# CertStack.net
KiCad netlist of a schematic drawn in EAGLE
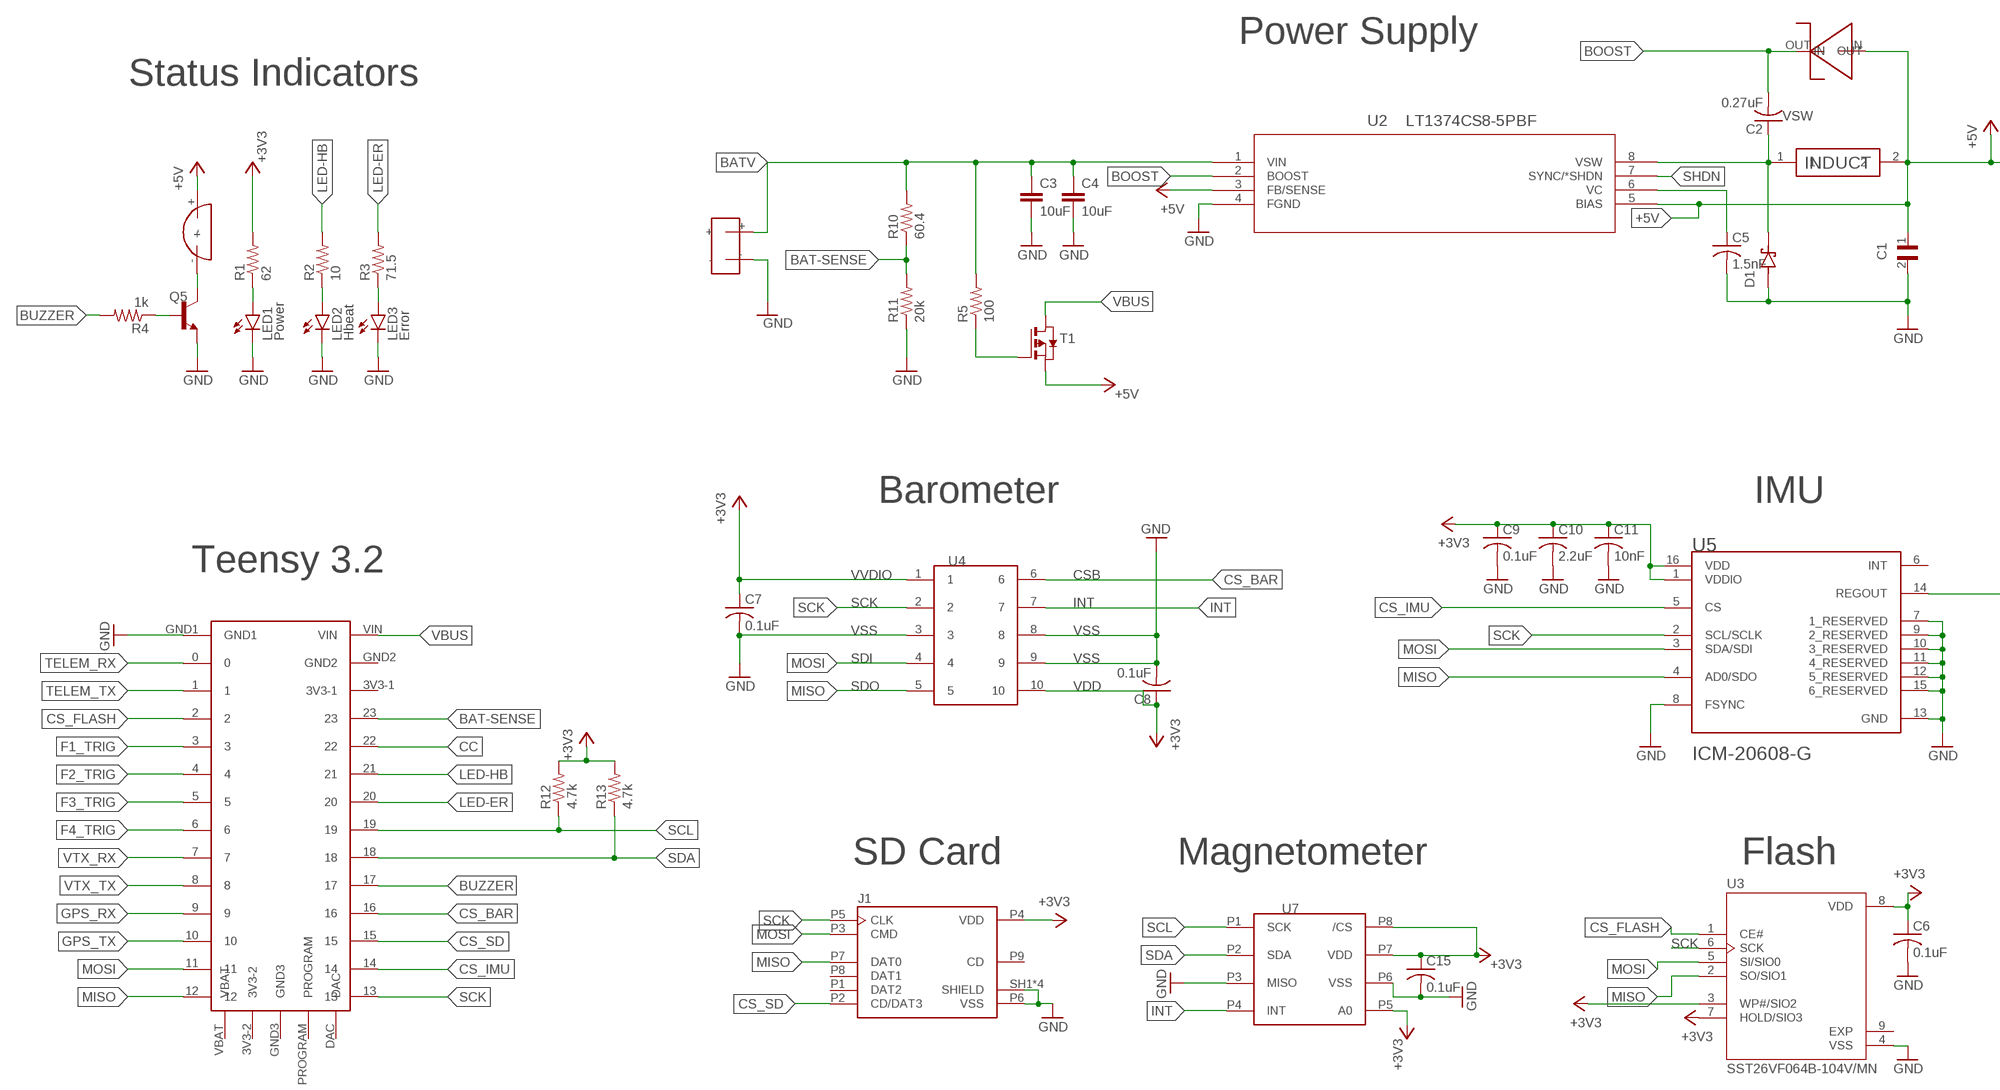
[diagram p0: schematic, sheet 1, part 1 of 2]
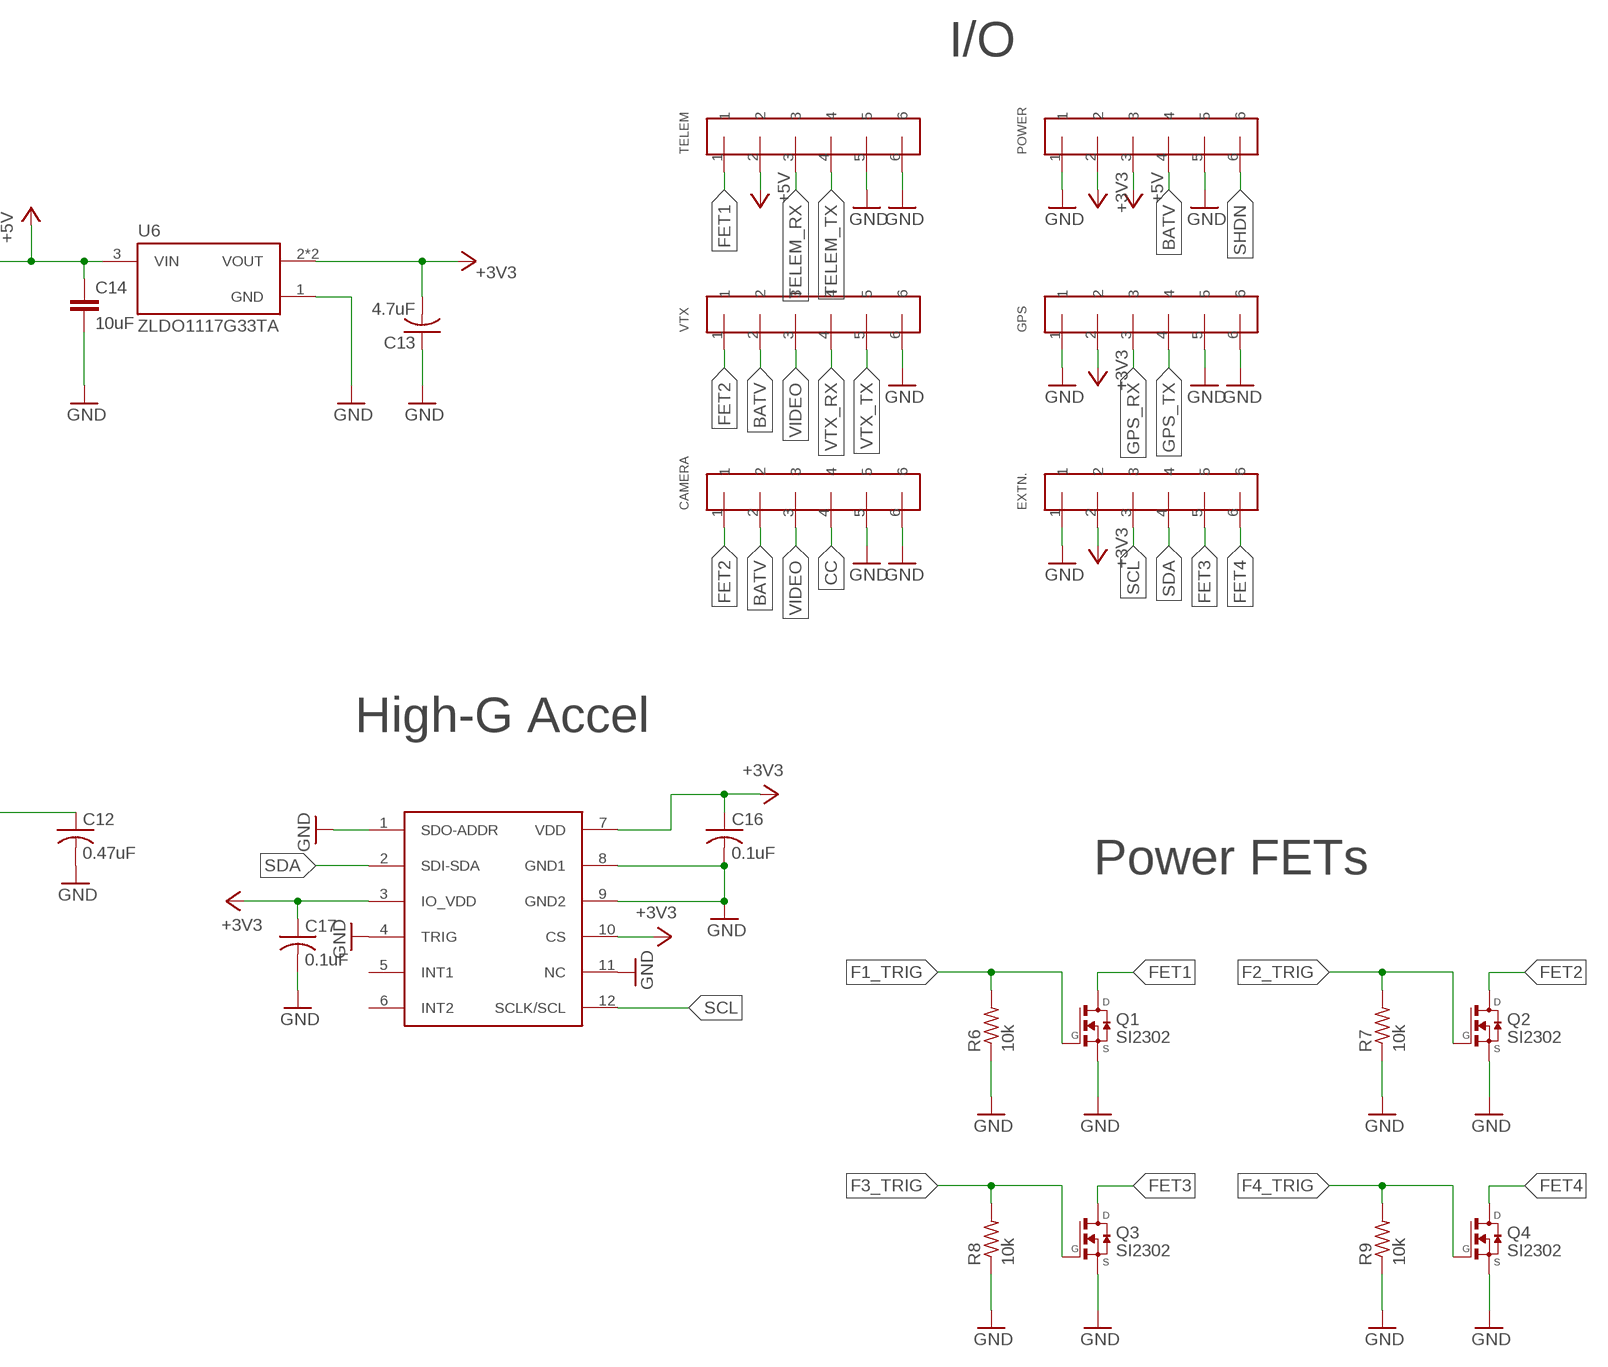
[diagram p1: schematic, sheet 1, part 2 of 2]

(export (version "E")
  (design (tool "Eeschema 10.0.6"))
  (components
    (comp (ref "BATT-CON")
      (value "PWR-AWG18")
      (footprint "eagle-import:PWR-AWG18")
      (libsource (lib "eagle-import") (part "PWR-AWG18"))
    )
    (comp (ref "C1")
      (value "T491X106K050AT")
      (footprint "eagle-import:CAPMP7343X430N")
      (fields (field (name "MF") "KEMET"))
      (libsource (lib "eagle-import") (part "T491X106K050AT"))
    )
    (comp (ref "C2")
      (value "0.27uF")
      (footprint "eagle-import:C0805")
      (libsource (lib "eagle-import") (part "C-USC0805"))
    )
    (comp (ref "C3")
      (value "10uF")
      (footprint "eagle-import:1206")
      (libsource (lib "eagle-import") (part "10UF-1206-6.3V-20%"))
    )
    (comp (ref "C4")
      (value "10uF")
      (footprint "eagle-import:1206")
      (libsource (lib "eagle-import") (part "10UF-1206-6.3V-20%"))
    )
    (comp (ref "C5")
      (value "1.5nF")
      (footprint "eagle-import:C0805")
      (libsource (lib "eagle-import") (part "C-USC0805"))
    )
    (comp (ref "C6")
      (value "0.1uF")
      (footprint "eagle-import:C0805")
      (libsource (lib "eagle-import") (part "C-USC0805"))
    )
    (comp (ref "C7")
      (value "0.1uF")
      (footprint "eagle-import:C0805")
      (libsource (lib "eagle-import") (part "C-USC0805"))
    )
    (comp (ref "C8")
      (value "0.1uF")
      (footprint "eagle-import:C0805")
      (libsource (lib "eagle-import") (part "C-USC0805"))
    )
    (comp (ref "C9")
      (value "0.1uF")
      (footprint "eagle-import:C0805")
      (libsource (lib "eagle-import") (part "C-USC0805"))
    )
    (comp (ref "C10")
      (value "2.2uF")
      (footprint "eagle-import:C0805")
      (libsource (lib "eagle-import") (part "C-USC0805"))
    )
    (comp (ref "C11")
      (value "10nF")
      (footprint "eagle-import:C0805")
      (libsource (lib "eagle-import") (part "C-USC0805"))
    )
    (comp (ref "C12")
      (value "0.47uF")
      (footprint "eagle-import:C0805")
      (libsource (lib "eagle-import") (part "C-USC0805"))
    )
    (comp (ref "C13")
      (value "4.7uF")
      (footprint "eagle-import:C0805")
      (libsource (lib "eagle-import") (part "C-USC0805"))
    )
    (comp (ref "C14")
      (value "10uF")
      (footprint "eagle-import:1206")
      (libsource (lib "eagle-import") (part "10UF-1206-6.3V-20%"))
    )
    (comp (ref "C15")
      (value "0.1uF")
      (footprint "eagle-import:C0805")
      (libsource (lib "eagle-import") (part "C-USC0805"))
    )
    (comp (ref "C16")
      (value "0.1uF")
      (footprint "eagle-import:C0805")
      (libsource (lib "eagle-import") (part "C-USC0805"))
    )
    (comp (ref "C17")
      (value "0.1uF")
      (footprint "eagle-import:C0805")
      (libsource (lib "eagle-import") (part "C-USC0805"))
    )
    (comp (ref "CAMERA")
      (value "JST-PH-6")
      (footprint "eagle-import:JST-PH-6")
      (libsource (lib "eagle-import") (part "JST-PH-6"))
    )
    (comp (ref "D1")
      (value "PMEG4020ETP,115")
      (footprint "eagle-import:SODFL4725X110N")
      (fields (field (name "MF") "Nexperia USA Inc."))
      (libsource (lib "eagle-import") (part "PMEG4020ETP,115"))
    )
    (comp (ref "D2")
      (value "DO-214AB")
      (footprint "eagle-import:DO-214AB")
      (fields (field (name "MF") "Littelfuse Inc."))
      (libsource (lib "eagle-import") (part "DO-214AB"))
    )
    (comp (ref "EXTN.")
      (value "JST-PH-6")
      (footprint "eagle-import:JST-PH-6")
      (libsource (lib "eagle-import") (part "JST-PH-6"))
    )
    (comp (ref "GPS")
      (value "JST-PH-6")
      (footprint "eagle-import:JST-PH-6")
      (libsource (lib "eagle-import") (part "JST-PH-6"))
    )
    (comp (ref "J1")
      (value "MEM2075-00-140-01-A")
      (footprint "eagle-import:GCT_MEM2075-00-140-01-A")
      (fields (field (name "MF") "Global Connector Technology"))
      (libsource (lib "eagle-import") (part "MEM2075-00-140-01-A"))
    )
    (comp (ref "L1")
      (value "IHLP3232DZER6R8M11")
      (footprint "eagle-import:IHLP3232DZER6R8M11")
      (libsource (lib "eagle-import") (part "IHLP3232DZER6R8M11"))
    )
    (comp (ref "LED1")
      (value "Power")
      (footprint "eagle-import:SML0805")
      (libsource (lib "eagle-import") (part "LEDSML0805"))
    )
    (comp (ref "LED2")
      (value "Hbeat")
      (footprint "eagle-import:SML0805")
      (libsource (lib "eagle-import") (part "LEDSML0805"))
    )
    (comp (ref "LED3")
      (value "Error")
      (footprint "eagle-import:SML0805")
      (libsource (lib "eagle-import") (part "LEDSML0805"))
    )
    (comp (ref "LS1")
      (value "CMT-8540S")
      (footprint "eagle-import:CMT-8540S")
      (libsource (lib "eagle-import") (part "CMT-8540S"))
    )
    (comp (ref "POWER")
      (value "JST-PH-6")
      (footprint "eagle-import:JST-PH-6")
      (libsource (lib "eagle-import") (part "JST-PH-6"))
    )
    (comp (ref "Q1")
      (value "SI2302")
      (footprint "eagle-import:SOT23")
      (fields (field (name "MF") "Vishay Siliconix"))
      (libsource (lib "eagle-import") (part "SI2302"))
    )
    (comp (ref "Q2")
      (value "SI2302")
      (footprint "eagle-import:SOT23")
      (fields (field (name "MF") "Vishay Siliconix"))
      (libsource (lib "eagle-import") (part "SI2302"))
    )
    (comp (ref "Q3")
      (value "SI2302")
      (footprint "eagle-import:SOT23")
      (fields (field (name "MF") "Vishay Siliconix"))
      (libsource (lib "eagle-import") (part "SI2302"))
    )
    (comp (ref "Q4")
      (value "SI2302")
      (footprint "eagle-import:SOT23")
      (fields (field (name "MF") "Vishay Siliconix"))
      (libsource (lib "eagle-import") (part "SI2302"))
    )
    (comp (ref "Q5")
      (value "MMBT2222A")
      (footprint "eagle-import:SOT23")
      (fields (field (name "MF") "Fairchild Semiconductor") (field (name "MP") "MMBT2222A."))
      (libsource (lib "eagle-import") (part "MMBT2222A"))
    )
    (comp (ref "R1")
      (value "62")
      (footprint "eagle-import:R0805")
      (libsource (lib "eagle-import") (part "R-US_R0805"))
    )
    (comp (ref "R2")
      (value "10")
      (footprint "eagle-import:R0805")
      (libsource (lib "eagle-import") (part "R-US_R0805"))
    )
    (comp (ref "R3")
      (value "71.5")
      (footprint "eagle-import:R0805")
      (libsource (lib "eagle-import") (part "R-US_R0805"))
    )
    (comp (ref "R4")
      (value "1k")
      (footprint "eagle-import:R0805")
      (libsource (lib "eagle-import") (part "R-US_R0805"))
    )
    (comp (ref "R5")
      (value "100")
      (footprint "eagle-import:R0805")
      (libsource (lib "eagle-import") (part "R-US_R0805"))
    )
    (comp (ref "R6")
      (value "10k")
      (footprint "eagle-import:R0805")
      (libsource (lib "eagle-import") (part "R-US_R0805"))
    )
    (comp (ref "R7")
      (value "10k")
      (footprint "eagle-import:R0805")
      (libsource (lib "eagle-import") (part "R-US_R0805"))
    )
    (comp (ref "R8")
      (value "10k")
      (footprint "eagle-import:R0805")
      (libsource (lib "eagle-import") (part "R-US_R0805"))
    )
    (comp (ref "R9")
      (value "10k")
      (footprint "eagle-import:R0805")
      (libsource (lib "eagle-import") (part "R-US_R0805"))
    )
    (comp (ref "R10")
      (value "60.4")
      (footprint "eagle-import:R0805")
      (libsource (lib "eagle-import") (part "R-US_R0805"))
    )
    (comp (ref "R11")
      (value "20k")
      (footprint "eagle-import:R0805")
      (libsource (lib "eagle-import") (part "R-US_R0805"))
    )
    (comp (ref "R12")
      (value "4.7k")
      (footprint "eagle-import:R0805")
      (libsource (lib "eagle-import") (part "R-US_R0805"))
    )
    (comp (ref "R13")
      (value "4.7k")
      (footprint "eagle-import:R0805")
      (libsource (lib "eagle-import") (part "R-US_R0805"))
    )
    (comp (ref "T1")
      (value "DMP3098L-7")
      (footprint "eagle-import:SOT-23")
      (libsource (lib "eagle-import") (part "PMOSSOT23"))
    )
    (comp (ref "TELEM")
      (value "JST-PH-6")
      (footprint "eagle-import:JST-PH-6")
      (libsource (lib "eagle-import") (part "JST-PH-6"))
    )
    (comp (ref "U1")
      (value "TEENSY-32")
      (footprint "eagle-import:TEENSY-32")
      (libsource (lib "eagle-import") (part "TEENSY-32"))
    )
    (comp (ref "U2")
      (value "LT1374CS8-5PBF")
      (footprint "eagle-import:SO-8_S")
      (fields (field (name "MF") "Analog Devices") (field (name "MP") "LT1374CS8-5#PBF"))
      (libsource (lib "eagle-import") (part "LT1374CS8-5PBF"))
    )
    (comp (ref "U3")
      (value "SST26VF064B-104V/MN")
      (footprint "eagle-import:SON127P600X800X80-9N")
      (fields (field (name "MF") "Microchip"))
      (libsource (lib "eagle-import") (part "SST26VF064B-104V/MN"))
    )
    (comp (ref "U4")
      (value "BMP384")
      (footprint "eagle-import:PQFN45P200X200X100-10N")
      (libsource (lib "eagle-import") (part "BMP384"))
    )
    (comp (ref "U5")
      (value "INVENSENSE_ICM-20608-GINVENSENSE_ICM-20608-G_0_0")
      (footprint "eagle-import:INVENSENSE_ICM-20608-G_0")
      (fields
        (field (name "DIGIKEY_PART_NUMBER") "1428-1052-1-ND")
        (field (name "MF") "InvenSense")
        (field (name "MOUSER_PART_NUMBER") "410-ICM-20608-G")
      )
      (libsource (lib "eagle-import") (part "INVENSENSE_ICM-20608-GINVENSENSE_ICM-20608-G_0_0"))
    )
    (comp (ref "U6")
      (value "ZLDO1117G33TA")
      (footprint "eagle-import:SOT230P700X180-4N")
      (fields (field (name "MF") "Diodes Inc."))
      (libsource (lib "eagle-import") (part "ZLDO1117G33TA"))
    )
    (comp (ref "U7")
      (value "MLX90395KDCMLX90395")
      (footprint "eagle-import:MLX90395KDC_FPRT")
      (libsource (lib "eagle-import") (part "MLX90395KDCMLX90395"))
    )
    (comp (ref "U8")
      (value "KIONIX_KXTJ3-1057")
      (footprint "eagle-import:KIONIX_KXTJ3-1057")
      (libsource (lib "eagle-import") (part "KIONIX_KXTJ3-1057"))
    )
    (comp (ref "VTX")
      (value "JST-PH-6")
      (footprint "eagle-import:JST-PH-6")
      (libsource (lib "eagle-import") (part "JST-PH-6"))
    )
  )
  (nets
    (net (code "1") (name "+3V3") (class "Default")
      (node (ref "C10") (pin "1") (pinfunction "1_1") (pintype "passive"))
      (node (ref "C11") (pin "1") (pinfunction "1_1") (pintype "passive"))
      (node (ref "C13") (pin "2") (pinfunction "2_2") (pintype "passive"))
      (node (ref "C15") (pin "1") (pinfunction "1_1") (pintype "passive"))
      (node (ref "C16") (pin "1") (pinfunction "1_1") (pintype "passive"))
      (node (ref "C17") (pin "1") (pinfunction "1_1") (pintype "passive"))
      (node (ref "C6") (pin "1") (pinfunction "1_1") (pintype "passive"))
      (node (ref "C7") (pin "1") (pinfunction "1_1") (pintype "passive"))
      (node (ref "C8") (pin "1") (pinfunction "1_1") (pintype "passive"))
      (node (ref "C9") (pin "1") (pinfunction "1_1") (pintype "passive"))
      (node (ref "EXTN.") (pin "2") (pinfunction "2_2") (pintype "bidirectional"))
      (node (ref "GPS") (pin "2") (pinfunction "2_2") (pintype "bidirectional"))
      (node (ref "J1") (pin "P4") (pinfunction "VDD_P4") (pintype "power_in"))
      (node (ref "POWER") (pin "2") (pinfunction "2_2") (pintype "bidirectional"))
      (node (ref "R1") (pin "2") (pinfunction "2_2") (pintype "passive"))
      (node (ref "R12") (pin "2") (pinfunction "2_2") (pintype "passive"))
      (node (ref "R13") (pin "2") (pinfunction "2_2") (pintype "passive"))
      (node (ref "U3") (pin "3") (pinfunction "WP#/SIO2_3") (pintype "bidirectional"))
      (node (ref "U3") (pin "7") (pinfunction "HOLD/SIO3_7") (pintype "bidirectional"))
      (node (ref "U3") (pin "8") (pinfunction "VDD_8") (pintype "power_in"))
      (node (ref "U4") (pin "1") (pinfunction "1_1") (pintype "bidirectional"))
      (node (ref "U4") (pin "10") (pinfunction "10_10") (pintype "bidirectional"))
      (node (ref "U5") (pin "1") (pinfunction "VDDIO_1") (pintype "power_in"))
      (node (ref "U5") (pin "16") (pinfunction "VDD_16") (pintype "power_in"))
      (node (ref "U6") (pin "2") (pinfunction "VOUT_2") (pintype "output"))
      (node (ref "U6") (pin "4") (pinfunction "VOUT_4") (pintype "output"))
      (node (ref "U7") (pin "P5") (pinfunction "A0_P5") (pintype "bidirectional"))
      (node (ref "U7") (pin "P7") (pinfunction "VDD_P7") (pintype "bidirectional"))
      (node (ref "U7") (pin "P8") (pinfunction "/CS_P8") (pintype "bidirectional"))
      (node (ref "U8") (pin "10") (pinfunction "CS_10") (pintype "bidirectional"))
      (node (ref "U8") (pin "3") (pinfunction "IO_VDD_3") (pintype "bidirectional"))
      (node (ref "U8") (pin "7") (pinfunction "VDD_7") (pintype "bidirectional"))
    )
    (net (code "2") (name "+5V") (class "Default")
      (node (ref "C1") (pin "1") (pinfunction "1_1") (pintype "passive"))
      (node (ref "C14") (pin "1") (pinfunction "1_1") (pintype "passive"))
      (node (ref "D2") (pin "IN") (pinfunction "IN_IN") (pintype "bidirectional"))
      (node (ref "L1") (pin "2") (pinfunction "2_2") (pintype "bidirectional"))
      (node (ref "LS1") (pin "+") (pinfunction "+_+") (pintype "bidirectional"))
      (node (ref "POWER") (pin "3") (pinfunction "3_3") (pintype "bidirectional"))
      (node (ref "T1") (pin "2") (pinfunction "S_2") (pintype "passive"))
      (node (ref "TELEM") (pin "2") (pinfunction "2_2") (pintype "bidirectional"))
      (node (ref "U2") (pin "3") (pinfunction "FB/SENSE_3") (pintype "input"))
      (node (ref "U2") (pin "5") (pinfunction "BIAS_5") (pintype "input"))
      (node (ref "U6") (pin "3") (pinfunction "VIN_3") (pintype "input"))
    )
    (net (code "3") (name "/VSW") (class "Default")
      (node (ref "C2") (pin "1") (pinfunction "1_1") (pintype "passive"))
      (node (ref "D1") (pin "1") (pinfunction "K_1") (pintype "passive"))
      (node (ref "L1") (pin "1") (pinfunction "1_1") (pintype "bidirectional"))
      (node (ref "U2") (pin "8") (pinfunction "VSW_8") (pintype "input"))
    )
    (net (code "4") (name "BAT-SENSE") (class "Default")
      (node (ref "R10") (pin "1") (pinfunction "1_1") (pintype "passive"))
      (node (ref "R11") (pin "2") (pinfunction "2_2") (pintype "passive"))
      (node (ref "U1") (pin "23") (pinfunction "23_23") (pintype "bidirectional"))
    )
    (net (code "5") (name "BATV") (class "Default")
      (node (ref "BATT-CON") (pin "+") (pinfunction "+_+") (pintype "bidirectional"))
      (node (ref "C3") (pin "1") (pinfunction "1_1") (pintype "passive"))
      (node (ref "C4") (pin "1") (pinfunction "1_1") (pintype "passive"))
      (node (ref "CAMERA") (pin "2") (pinfunction "2_2") (pintype "bidirectional"))
      (node (ref "POWER") (pin "4") (pinfunction "4_4") (pintype "bidirectional"))
      (node (ref "R10") (pin "2") (pinfunction "2_2") (pintype "passive"))
      (node (ref "R5") (pin "2") (pinfunction "2_2") (pintype "passive"))
      (node (ref "U2") (pin "1") (pinfunction "VIN_1") (pintype "input"))
      (node (ref "VTX") (pin "2") (pinfunction "2_2") (pintype "bidirectional"))
    )
    (net (code "6") (name "BOOST") (class "Default")
      (node (ref "C2") (pin "2") (pinfunction "2_2") (pintype "passive"))
      (node (ref "D2") (pin "OUT") (pinfunction "OUT_OUT") (pintype "bidirectional"))
      (node (ref "U2") (pin "2") (pinfunction "BOOST_2") (pintype "input"))
    )
    (net (code "7") (name "BUZZER") (class "Default")
      (node (ref "R4") (pin "2") (pinfunction "2_2") (pintype "passive"))
      (node (ref "U1") (pin "17") (pinfunction "17_17") (pintype "bidirectional"))
    )
    (net (code "8") (name "CC") (class "Default")
      (node (ref "CAMERA") (pin "4") (pinfunction "4_4") (pintype "bidirectional"))
      (node (ref "U1") (pin "22") (pinfunction "22_22") (pintype "bidirectional"))
    )
    (net (code "9") (name "CS_BAR") (class "Default")
      (node (ref "U1") (pin "16") (pinfunction "16_16") (pintype "bidirectional"))
      (node (ref "U4") (pin "6") (pinfunction "6_6") (pintype "bidirectional"))
    )
    (net (code "10") (name "CS_FLASH") (class "Default")
      (node (ref "U1") (pin "2") (pinfunction "2_2") (pintype "bidirectional"))
      (node (ref "U3") (pin "1") (pinfunction "CE#_1") (pintype "input"))
    )
    (net (code "11") (name "CS_IMU") (class "Default")
      (node (ref "U1") (pin "14") (pinfunction "14_14") (pintype "bidirectional"))
      (node (ref "U5") (pin "5") (pinfunction "CS_5") (pintype "input"))
    )
    (net (code "12") (name "CS_SD") (class "Default")
      (node (ref "J1") (pin "P2") (pinfunction "CD/DAT3_P2") (pintype "bidirectional"))
      (node (ref "U1") (pin "15") (pinfunction "15_15") (pintype "bidirectional"))
    )
    (net (code "13") (name "F1_TRIG") (class "Default")
      (node (ref "Q1") (pin "1") (pinfunction "G_1") (pintype "passive"))
      (node (ref "R6") (pin "2") (pinfunction "2_2") (pintype "passive"))
      (node (ref "U1") (pin "3") (pinfunction "3_3") (pintype "bidirectional"))
    )
    (net (code "14") (name "F2_TRIG") (class "Default")
      (node (ref "Q2") (pin "1") (pinfunction "G_1") (pintype "passive"))
      (node (ref "R7") (pin "2") (pinfunction "2_2") (pintype "passive"))
      (node (ref "U1") (pin "4") (pinfunction "4_4") (pintype "bidirectional"))
    )
    (net (code "15") (name "F3_TRIG") (class "Default")
      (node (ref "Q3") (pin "1") (pinfunction "G_1") (pintype "passive"))
      (node (ref "R8") (pin "2") (pinfunction "2_2") (pintype "passive"))
      (node (ref "U1") (pin "5") (pinfunction "5_5") (pintype "bidirectional"))
    )
    (net (code "16") (name "F4_TRIG") (class "Default")
      (node (ref "Q4") (pin "1") (pinfunction "G_1") (pintype "passive"))
      (node (ref "R9") (pin "2") (pinfunction "2_2") (pintype "passive"))
      (node (ref "U1") (pin "6") (pinfunction "6_6") (pintype "bidirectional"))
    )
    (net (code "17") (name "FET1") (class "Default")
      (node (ref "Q1") (pin "3") (pinfunction "D_3") (pintype "passive"))
      (node (ref "TELEM") (pin "1") (pinfunction "1_1") (pintype "bidirectional"))
    )
    (net (code "18") (name "FET2") (class "Default")
      (node (ref "CAMERA") (pin "1") (pinfunction "1_1") (pintype "bidirectional"))
      (node (ref "Q2") (pin "3") (pinfunction "D_3") (pintype "passive"))
      (node (ref "VTX") (pin "1") (pinfunction "1_1") (pintype "bidirectional"))
    )
    (net (code "19") (name "FET3") (class "Default")
      (node (ref "EXTN.") (pin "5") (pinfunction "5_5") (pintype "bidirectional"))
      (node (ref "Q3") (pin "3") (pinfunction "D_3") (pintype "passive"))
    )
    (net (code "20") (name "FET4") (class "Default")
      (node (ref "EXTN.") (pin "6") (pinfunction "6_6") (pintype "bidirectional"))
      (node (ref "Q4") (pin "3") (pinfunction "D_3") (pintype "passive"))
    )
    (net (code "21") (name "GND") (class "Default")
      (node (ref "BATT-CON") (pin "-") (pinfunction "-_-") (pintype "bidirectional"))
      (node (ref "C1") (pin "2") (pinfunction "2_2") (pintype "passive"))
      (node (ref "C10") (pin "2") (pinfunction "2_2") (pintype "passive"))
      (node (ref "C11") (pin "2") (pinfunction "2_2") (pintype "passive"))
      (node (ref "C12") (pin "2") (pinfunction "2_2") (pintype "passive"))
      (node (ref "C13") (pin "1") (pinfunction "1_1") (pintype "passive"))
      (node (ref "C14") (pin "2") (pinfunction "2_2") (pintype "passive"))
      (node (ref "C15") (pin "2") (pinfunction "2_2") (pintype "passive"))
      (node (ref "C16") (pin "2") (pinfunction "2_2") (pintype "passive"))
      (node (ref "C17") (pin "2") (pinfunction "2_2") (pintype "passive"))
      (node (ref "C3") (pin "2") (pinfunction "2_2") (pintype "passive"))
      (node (ref "C4") (pin "2") (pinfunction "2_2") (pintype "passive"))
      (node (ref "C5") (pin "2") (pinfunction "2_2") (pintype "passive"))
      (node (ref "C6") (pin "2") (pinfunction "2_2") (pintype "passive"))
      (node (ref "C7") (pin "2") (pinfunction "2_2") (pintype "passive"))
      (node (ref "C8") (pin "2") (pinfunction "2_2") (pintype "passive"))
      (node (ref "C9") (pin "2") (pinfunction "2_2") (pintype "passive"))
      (node (ref "CAMERA") (pin "5") (pinfunction "5_5") (pintype "bidirectional"))
      (node (ref "CAMERA") (pin "6") (pinfunction "6_6") (pintype "bidirectional"))
      (node (ref "D1") (pin "2") (pinfunction "A_2") (pintype "passive"))
      (node (ref "EXTN.") (pin "1") (pinfunction "1_1") (pintype "bidirectional"))
      (node (ref "GPS") (pin "1") (pinfunction "1_1") (pintype "bidirectional"))
      (node (ref "GPS") (pin "5") (pinfunction "5_5") (pintype "bidirectional"))
      (node (ref "GPS") (pin "6") (pinfunction "6_6") (pintype "bidirectional"))
      (node (ref "J1") (pin "P6") (pinfunction "VSS_P6") (pintype "power_in"))
      (node (ref "J1") (pin "SH1") (pinfunction "SHIELD_SH1") (pintype "power_in"))
      (node (ref "J1") (pin "SH2") (pinfunction "SHIELD_SH2") (pintype "power_in"))
      (node (ref "J1") (pin "SH3") (pinfunction "SHIELD_SH3") (pintype "power_in"))
      (node (ref "J1") (pin "SH4") (pinfunction "SHIELD_SH4") (pintype "power_in"))
      (node (ref "LED1") (pin "C") (pinfunction "C_C") (pintype "passive"))
      (node (ref "LED2") (pin "C") (pinfunction "C_C") (pintype "passive"))
      (node (ref "LED3") (pin "C") (pinfunction "C_C") (pintype "passive"))
      (node (ref "POWER") (pin "1") (pinfunction "1_1") (pintype "bidirectional"))
      (node (ref "POWER") (pin "5") (pinfunction "5_5") (pintype "bidirectional"))
      (node (ref "Q1") (pin "2") (pinfunction "S_2") (pintype "passive"))
      (node (ref "Q2") (pin "2") (pinfunction "S_2") (pintype "passive"))
      (node (ref "Q3") (pin "2") (pinfunction "S_2") (pintype "passive"))
      (node (ref "Q4") (pin "2") (pinfunction "S_2") (pintype "passive"))
      (node (ref "Q5") (pin "2") (pinfunction "E_2") (pintype "passive"))
      (node (ref "R11") (pin "1") (pinfunction "1_1") (pintype "passive"))
      (node (ref "R6") (pin "1") (pinfunction "1_1") (pintype "passive"))
      (node (ref "R7") (pin "1") (pinfunction "1_1") (pintype "passive"))
      (node (ref "R8") (pin "1") (pinfunction "1_1") (pintype "passive"))
      (node (ref "R9") (pin "1") (pinfunction "1_1") (pintype "passive"))
      (node (ref "TELEM") (pin "5") (pinfunction "5_5") (pintype "bidirectional"))
      (node (ref "TELEM") (pin "6") (pinfunction "6_6") (pintype "bidirectional"))
      (node (ref "U1") (pin "GND1") (pinfunction "GND1_GND1") (pintype "bidirectional"))
      (node (ref "U2") (pin "4") (pinfunction "FGND_4") (pintype "power_in"))
      (node (ref "U3") (pin "4") (pinfunction "VSS_4") (pintype "power_in"))
      (node (ref "U4") (pin "3") (pinfunction "3_3") (pintype "bidirectional"))
      (node (ref "U4") (pin "8") (pinfunction "8_8") (pintype "bidirectional"))
      (node (ref "U4") (pin "9") (pinfunction "9_9") (pintype "bidirectional"))
      (node (ref "U5") (pin "10") (pinfunction "3_RESERVED_10") (pintype "passive"))
      (node (ref "U5") (pin "11") (pinfunction "4_RESERVED_11") (pintype "passive"))
      (node (ref "U5") (pin "12") (pinfunction "5_RESERVED_12") (pintype "passive"))
      (node (ref "U5") (pin "13") (pinfunction "GND_13") (pintype "power_in"))
      (node (ref "U5") (pin "15") (pinfunction "6_RESERVED_15") (pintype "passive"))
      (node (ref "U5") (pin "7") (pinfunction "1_RESERVED_7") (pintype "passive"))
      (node (ref "U5") (pin "8") (pinfunction "FSYNC_8") (pintype "input"))
      (node (ref "U5") (pin "9") (pinfunction "2_RESERVED_9") (pintype "passive"))
      (node (ref "U6") (pin "1") (pinfunction "GND_1") (pintype "power_in"))
      (node (ref "U7") (pin "P3") (pinfunction "MISO_P3") (pintype "bidirectional"))
      (node (ref "U7") (pin "P6") (pinfunction "VSS_P6") (pintype "bidirectional"))
      (node (ref "U8") (pin "1") (pinfunction "SDO-ADDR_1") (pintype "bidirectional"))
      (node (ref "U8") (pin "11") (pinfunction "NC_11") (pintype "bidirectional"))
      (node (ref "U8") (pin "4") (pinfunction "TRIG_4") (pintype "bidirectional"))
      (node (ref "U8") (pin "8") (pinfunction "GND1_8") (pintype "bidirectional"))
      (node (ref "U8") (pin "9") (pinfunction "GND2_9") (pintype "bidirectional"))
      (node (ref "VTX") (pin "6") (pinfunction "6_6") (pintype "bidirectional"))
    )
    (net (code "22") (name "GPS_RX") (class "Default")
      (node (ref "GPS") (pin "3") (pinfunction "3_3") (pintype "bidirectional"))
      (node (ref "U1") (pin "9") (pinfunction "9_9") (pintype "bidirectional"))
    )
    (net (code "23") (name "GPS_TX") (class "Default")
      (node (ref "GPS") (pin "4") (pinfunction "4_4") (pintype "bidirectional"))
      (node (ref "U1") (pin "10") (pinfunction "10_10") (pintype "bidirectional"))
    )
    (net (code "24") (name "INT") (class "Default")
      (node (ref "U4") (pin "7") (pinfunction "7_7") (pintype "bidirectional"))
    )
    (net (code "25") (name "LED-ER") (class "Default")
      (node (ref "R3") (pin "2") (pinfunction "2_2") (pintype "passive"))
      (node (ref "U1") (pin "20") (pinfunction "20_20") (pintype "bidirectional"))
    )
    (net (code "26") (name "LED-HB") (class "Default")
      (node (ref "R2") (pin "2") (pinfunction "2_2") (pintype "passive"))
      (node (ref "U1") (pin "21") (pinfunction "21_21") (pintype "bidirectional"))
    )
    (net (code "27") (name "MISO") (class "Default")
      (node (ref "J1") (pin "P7") (pinfunction "DAT0_P7") (pintype "bidirectional"))
      (node (ref "U1") (pin "12") (pinfunction "12_12") (pintype "bidirectional"))
      (node (ref "U3") (pin "2") (pinfunction "SO/SIO1_2") (pintype "bidirectional"))
      (node (ref "U4") (pin "5") (pinfunction "5_5") (pintype "bidirectional"))
      (node (ref "U5") (pin "4") (pinfunction "AD0/SDO_4") (pintype "input"))
    )
    (net (code "28") (name "MOSI") (class "Default")
      (node (ref "J1") (pin "P3") (pinfunction "CMD_P3") (pintype "bidirectional"))
      (node (ref "U1") (pin "11") (pinfunction "11_11") (pintype "bidirectional"))
      (node (ref "U3") (pin "5") (pinfunction "SI/SIO0_5") (pintype "bidirectional"))
      (node (ref "U4") (pin "4") (pinfunction "4_4") (pintype "bidirectional"))
      (node (ref "U5") (pin "3") (pinfunction "SDA/SDI_3") (pintype "bidirectional"))
    )
    (net (code "29") (name "Net-(LED1-PadA)") (class "Default")
      (node (ref "LED1") (pin "A") (pinfunction "A_A") (pintype "passive"))
      (node (ref "R1") (pin "1") (pinfunction "1_1") (pintype "passive"))
    )
    (net (code "30") (name "Net-(LED2-PadA)") (class "Default")
      (node (ref "LED2") (pin "A") (pinfunction "A_A") (pintype "passive"))
      (node (ref "R2") (pin "1") (pinfunction "1_1") (pintype "passive"))
    )
    (net (code "31") (name "Net-(LED3-PadA)") (class "Default")
      (node (ref "LED3") (pin "A") (pinfunction "A_A") (pintype "passive"))
      (node (ref "R3") (pin "1") (pinfunction "1_1") (pintype "passive"))
    )
    (net (code "32") (name "Net-(Q5-B)") (class "Default")
      (node (ref "Q5") (pin "1") (pinfunction "B_1") (pintype "passive"))
      (node (ref "R4") (pin "1") (pinfunction "1_1") (pintype "passive"))
    )
    (net (code "33") (name "Net-(Q5-C)") (class "Default")
      (node (ref "LS1") (pin "-") (pinfunction "-_-") (pintype "bidirectional"))
      (node (ref "Q5") (pin "3") (pinfunction "C_3") (pintype "passive"))
    )
    (net (code "34") (name "Net-(T1-G)") (class "Default")
      (node (ref "R5") (pin "1") (pinfunction "1_1") (pintype "passive"))
      (node (ref "T1") (pin "3") (pinfunction "G_3") (pintype "passive"))
    )
    (net (code "35") (name "Net-(U2-VC)") (class "Default")
      (node (ref "C5") (pin "1") (pinfunction "1_1") (pintype "passive"))
      (node (ref "U2") (pin "6") (pinfunction "VC_6") (pintype "output"))
    )
    (net (code "36") (name "Net-(U5-REGOUT)") (class "Default")
      (node (ref "C12") (pin "1") (pinfunction "1_1") (pintype "passive"))
      (node (ref "U5") (pin "14") (pinfunction "REGOUT_14") (pintype "power_in"))
    )
    (net (code "37") (name "SCK") (class "Default")
      (node (ref "J1") (pin "P5") (pinfunction "CLK_P5") (pintype "bidirectional"))
      (node (ref "U1") (pin "13") (pinfunction "13_13") (pintype "bidirectional"))
      (node (ref "U3") (pin "6") (pinfunction "SCK_6") (pintype "input"))
      (node (ref "U4") (pin "2") (pinfunction "2_2") (pintype "bidirectional"))
      (node (ref "U5") (pin "2") (pinfunction "SCL/SCLK_2") (pintype "input"))
    )
    (net (code "38") (name "SCL") (class "Default")
      (node (ref "EXTN.") (pin "3") (pinfunction "3_3") (pintype "bidirectional"))
      (node (ref "R12") (pin "1") (pinfunction "1_1") (pintype "passive"))
      (node (ref "U1") (pin "19") (pinfunction "19_19") (pintype "bidirectional"))
      (node (ref "U7") (pin "P1") (pinfunction "SCK_P1") (pintype "bidirectional"))
      (node (ref "U8") (pin "12") (pinfunction "SCLK/SCL_12") (pintype "bidirectional"))
    )
    (net (code "39") (name "SDA") (class "Default")
      (node (ref "EXTN.") (pin "4") (pinfunction "4_4") (pintype "bidirectional"))
      (node (ref "R13") (pin "1") (pinfunction "1_1") (pintype "passive"))
      (node (ref "U1") (pin "18") (pinfunction "18_18") (pintype "bidirectional"))
      (node (ref "U7") (pin "P2") (pinfunction "SDA_P2") (pintype "bidirectional"))
      (node (ref "U8") (pin "2") (pinfunction "SDI-SDA_2") (pintype "bidirectional"))
    )
    (net (code "40") (name "SHDN") (class "Default")
      (node (ref "POWER") (pin "6") (pinfunction "6_6") (pintype "bidirectional"))
      (node (ref "U2") (pin "7") (pinfunction "SYNC/*SHDN_7") (pintype "bidirectional"))
    )
    (net (code "41") (name "TELEM_RX") (class "Default")
      (node (ref "TELEM") (pin "3") (pinfunction "3_3") (pintype "bidirectional"))
      (node (ref "U1") (pin "0") (pinfunction "0_0") (pintype "bidirectional"))
    )
    (net (code "42") (name "TELEM_TX") (class "Default")
      (node (ref "TELEM") (pin "4") (pinfunction "4_4") (pintype "bidirectional"))
      (node (ref "U1") (pin "1") (pinfunction "1_1") (pintype "bidirectional"))
    )
    (net (code "43") (name "VBUS") (class "Default")
      (node (ref "T1") (pin "1") (pinfunction "D_1") (pintype "passive"))
      (node (ref "U1") (pin "VIN") (pinfunction "VIN_VIN") (pintype "bidirectional"))
    )
    (net (code "44") (name "VIDEO") (class "Default")
      (node (ref "CAMERA") (pin "3") (pinfunction "3_3") (pintype "bidirectional"))
      (node (ref "VTX") (pin "3") (pinfunction "3_3") (pintype "bidirectional"))
    )
    (net (code "45") (name "VTX_RX") (class "Default")
      (node (ref "U1") (pin "7") (pinfunction "7_7") (pintype "bidirectional"))
      (node (ref "VTX") (pin "4") (pinfunction "4_4") (pintype "bidirectional"))
    )
    (net (code "46") (name "VTX_TX") (class "Default")
      (node (ref "U1") (pin "8") (pinfunction "8_8") (pintype "bidirectional"))
      (node (ref "VTX") (pin "5") (pinfunction "5_5") (pintype "bidirectional"))
    )
    (net (code "47") (name "unconnected-(J1-CD-PadP9)") (class "Default")
      (node (ref "J1") (pin "P9") (pinfunction "CD_P9") (pintype "passive"))
    )
    (net (code "48") (name "unconnected-(J1-DAT1-PadP8)") (class "Default")
      (node (ref "J1") (pin "P8") (pinfunction "DAT1_P8") (pintype "bidirectional"))
    )
    (net (code "49") (name "unconnected-(J1-DAT2-PadP1)") (class "Default")
      (node (ref "J1") (pin "P1") (pinfunction "DAT2_P1") (pintype "bidirectional"))
    )
    (net (code "50") (name "unconnected-(U1-Pad3V3-1)") (class "Default")
      (node (ref "U1") (pin "3V3-1") (pinfunction "3V3-1_3V3-1") (pintype "bidirectional"))
    )
    (net (code "51") (name "unconnected-(U1-Pad3V3-2)") (class "Default")
      (node (ref "U1") (pin "3V3-2") (pinfunction "3V3-2_3V3-2") (pintype "bidirectional"))
    )
    (net (code "52") (name "unconnected-(U1-PadDAC)") (class "Default")
      (node (ref "U1") (pin "DAC") (pinfunction "DAC_DAC") (pintype "bidirectional"))
    )
    (net (code "53") (name "unconnected-(U1-PadGND2)") (class "Default")
      (node (ref "U1") (pin "GND2") (pinfunction "GND2_GND2") (pintype "bidirectional"))
    )
    (net (code "54") (name "unconnected-(U1-PadGND3)") (class "Default")
      (node (ref "U1") (pin "GND3") (pinfunction "GND3_GND3") (pintype "bidirectional"))
    )
    (net (code "55") (name "unconnected-(U1-PadPROGRAM)") (class "Default")
      (node (ref "U1") (pin "PROGRAM") (pinfunction "PROGRAM_PROGRAM") (pintype "bidirectional"))
    )
    (net (code "56") (name "unconnected-(U1-PadVBAT)") (class "Default")
      (node (ref "U1") (pin "VBAT") (pinfunction "VBAT_VBAT") (pintype "bidirectional"))
    )
    (net (code "57") (name "unconnected-(U3-EXP-Pad9)") (class "Default")
      (node (ref "U3") (pin "9") (pinfunction "EXP_9") (pintype "passive"))
    )
    (net (code "58") (name "unconnected-(U5-INT-Pad6)") (class "Default")
      (node (ref "U5") (pin "6") (pinfunction "INT_6") (pintype "output"))
    )
    (net (code "59") (name "unconnected-(U7-INT-PadP4)") (class "Default")
      (node (ref "U7") (pin "P4") (pinfunction "INT_P4") (pintype "bidirectional"))
    )
    (net (code "60") (name "unconnected-(U8-INT1-Pad5)") (class "Default")
      (node (ref "U8") (pin "5") (pinfunction "INT1_5") (pintype "bidirectional"))
    )
    (net (code "61") (name "unconnected-(U8-INT2-Pad6)") (class "Default")
      (node (ref "U8") (pin "6") (pinfunction "INT2_6") (pintype "bidirectional"))
    )
  )
)
